# Picc.net
KiCad netlist of a schematic drawn in Altium Designer
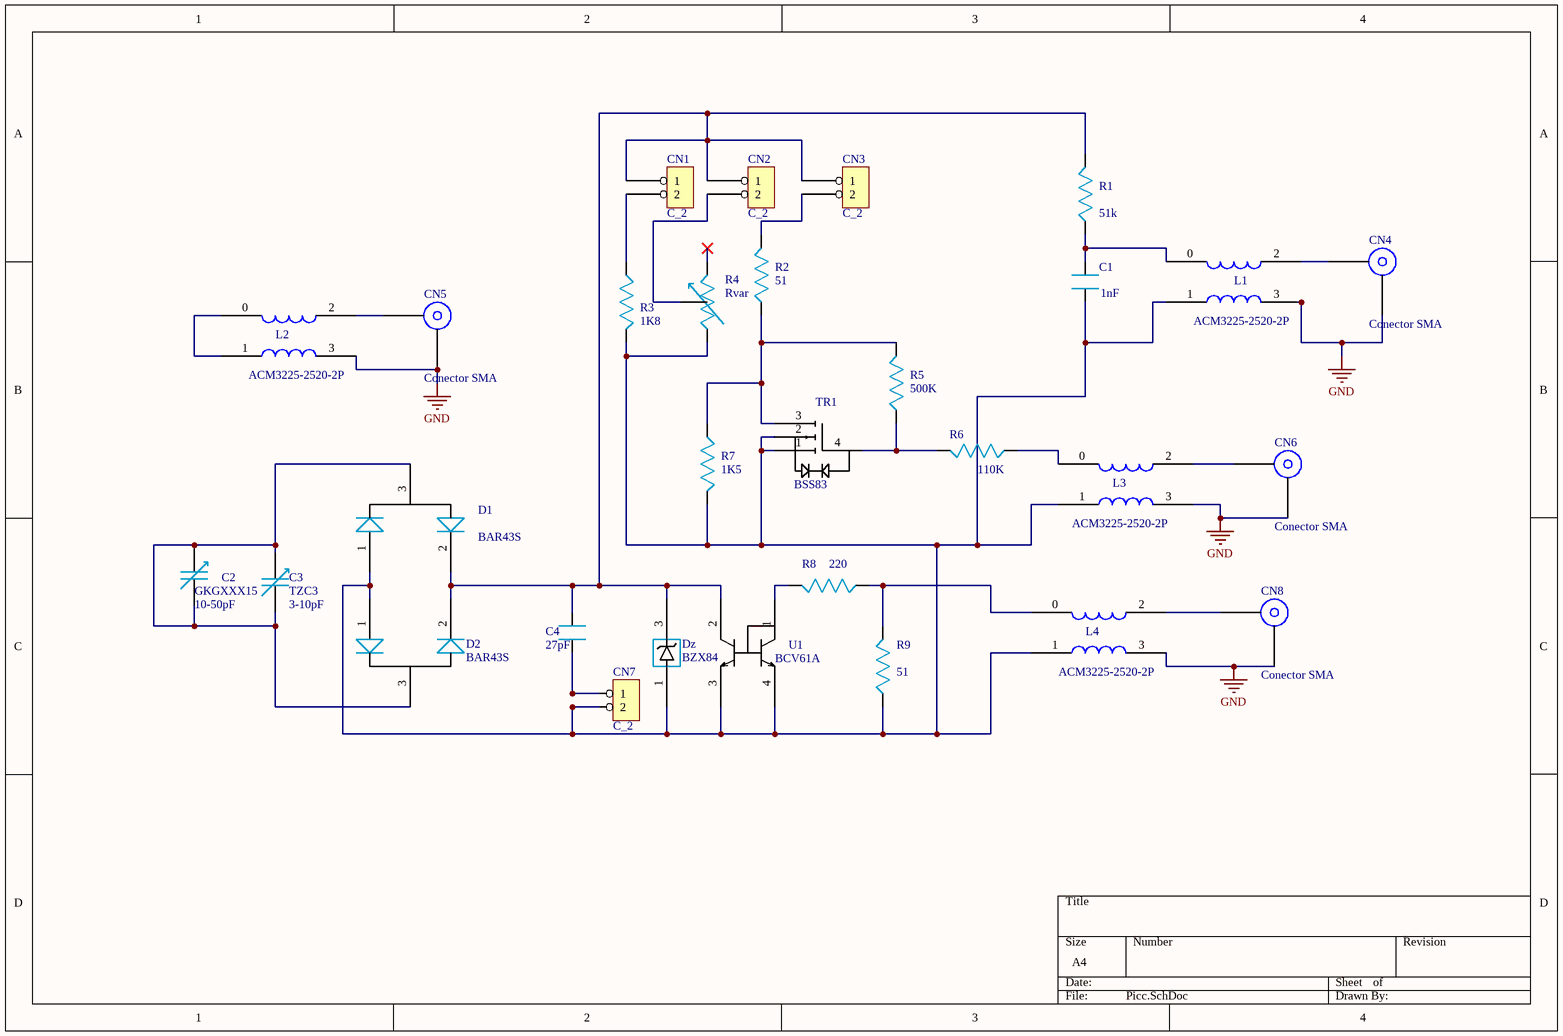
[diagram p0: Picc.SchDoc]

(export (version "E")
  (design (tool "Eeschema 10.0.6"))
  (components
    (comp (ref "C1")
      (value "1nF")
      (footprint "C_1210")
      (description "Ceramic Capacitor")
      (libsource (lib "BasicosyConectores") (part "Cap"))
    )
    (comp (ref "C2")
      (value "GKGXXX15")
      (footprint "GKGXXX15")
      (description "10")
      (fields (field (name "ALTIUM_UNNAMED_1") "10-50pF"))
      (libsource (lib "BasicosyConectores") (part "GKGXXX15"))
    )
    (comp (ref "C3")
      (value "TZC3")
      (footprint "TZC3")
      (fields (field (name "ALTIUM_UNNAMED_1") "3-10pF"))
      (libsource (lib "BasicosyConectores") (part "TZC3"))
    )
    (comp (ref "C4")
      (value "27pF")
      (footprint "C_1210")
      (description "Ceramic Capacitor")
      (libsource (lib "BasicosyConectores") (part "Cap"))
    )
    (comp (ref "CN1")
      (value "C_2")
      (footprint "2x1 Pin Array")
      (description "Conector 2 pines")
      (libsource (lib "BasicosyConectores") (part "C_2"))
    )
    (comp (ref "CN2")
      (value "C_2")
      (footprint "2x1 Pin Array")
      (description "Conector 2 pines")
      (libsource (lib "BasicosyConectores") (part "C_2"))
    )
    (comp (ref "CN3")
      (value "C_2")
      (footprint "2x1 Pin Array")
      (description "Conector 2 pines")
      (libsource (lib "BasicosyConectores") (part "C_2"))
    )
    (comp (ref "CN4")
      (value "Conector SMA")
      (footprint "Conector SMA")
      (description "Conector 2 pines")
      (libsource (lib "BasicosyConectores") (part "Conector SMA"))
    )
    (comp (ref "CN5")
      (value "Conector SMA")
      (footprint "Conector SMA")
      (description "Conector 2 pines")
      (libsource (lib "BasicosyConectores") (part "Conector SMA"))
    )
    (comp (ref "CN6")
      (value "Conector SMA")
      (footprint "Conector SMA")
      (description "Conector 2 pines")
      (libsource (lib "BasicosyConectores") (part "Conector SMA"))
    )
    (comp (ref "CN7")
      (value "C_2")
      (footprint "2x1 Pin Array")
      (description "Conector 2 pines")
      (libsource (lib "BasicosyConectores") (part "C_2"))
    )
    (comp (ref "CN8")
      (value "Conector SMA")
      (footprint "Conector SMA")
      (description "Conector 2 pines")
      (libsource (lib "BasicosyConectores") (part "Conector SMA"))
    )
    (comp (ref "D1")
      (value "BAR43S")
      (footprint "BAR43S")
      (libsource (lib "BasicosyConectores") (part "BAR43S"))
    )
    (comp (ref "D2")
      (value "BAR43S")
      (footprint "BAR43S")
      (libsource (lib "BasicosyConectores") (part "BAR43S"))
    )
    (comp (ref "Dz")
      (value "BZX84")
      (footprint "BZX84")
      (libsource (lib "BasicosyConectores") (part "BZX84"))
    )
    (comp (ref "L1")
      (value "ACM3225-2520-2P")
      (footprint "ACM3225.2520-2P")
      (libsource (lib "BasicosyConectores") (part "ACM3225-2520-2P"))
    )
    (comp (ref "L2")
      (value "ACM3225-2520-2P")
      (footprint "ACM3225.2520-2P")
      (libsource (lib "BasicosyConectores") (part "ACM3225-2520-2P"))
    )
    (comp (ref "L3")
      (value "ACM3225-2520-2P")
      (footprint "ACM3225.2520-2P")
      (libsource (lib "BasicosyConectores") (part "ACM3225-2520-2P"))
    )
    (comp (ref "L4")
      (value "ACM3225-2520-2P")
      (footprint "ACM3225.2520-2P")
      (libsource (lib "BasicosyConectores") (part "ACM3225-2520-2P"))
    )
    (comp (ref "R1")
      (value "51k")
      (footprint "R_1210")
      (description "Chip Resistor")
      (libsource (lib "BasicosyConectores") (part "R"))
    )
    (comp (ref "R2")
      (value "51")
      (footprint "R_1210")
      (description "Chip Resistor")
      (libsource (lib "BasicosyConectores") (part "R"))
    )
    (comp (ref "R3")
      (value "1K8")
      (footprint "R_1210")
      (description "Chip Resistor")
      (libsource (lib "BasicosyConectores") (part "R"))
    )
    (comp (ref "R4")
      (value "Rvar")
      (footprint "Bourns 3224W")
      (description "SMD Potentiometer")
      (libsource (lib "BasicosyConectores") (part "Rvar"))
    )
    (comp (ref "R5")
      (value "500K")
      (footprint "R_1210")
      (description "Chip Resistor")
      (libsource (lib "BasicosyConectores") (part "R"))
    )
    (comp (ref "R6")
      (value "110K")
      (footprint "R_1210")
      (description "Chip Resistor")
      (libsource (lib "BasicosyConectores") (part "R"))
    )
    (comp (ref "R7")
      (value "1K5")
      (footprint "R_1210")
      (description "Chip Resistor")
      (libsource (lib "BasicosyConectores") (part "R"))
    )
    (comp (ref "R8")
      (value "220")
      (footprint "R_1210")
      (description "Chip Resistor")
      (libsource (lib "BasicosyConectores") (part "R"))
    )
    (comp (ref "R9")
      (value "51")
      (footprint "R_1210")
      (description "Chip Resistor")
      (libsource (lib "BasicosyConectores") (part "R"))
    )
    (comp (ref "TR1")
      (value "BSS83")
      (footprint "BSS83")
      (libsource (lib "BasicosyConectores") (part "BSS83"))
    )
    (comp (ref "U1")
      (value "BCV61A")
      (footprint "BCV61A")
      (libsource (lib "BasicosyConectores") (part "BCV61A"))
    )
  )
  (nets
    (net (code "1") (name "GND") (class "Default")
      (node (ref "CN4") (pin "1") (pinfunction "1_1") (pintype "passive"))
      (node (ref "CN5") (pin "1") (pinfunction "1_1") (pintype "passive"))
      (node (ref "CN6") (pin "1") (pinfunction "1_1") (pintype "passive"))
      (node (ref "CN8") (pin "1") (pinfunction "1_1") (pintype "passive"))
      (node (ref "L1") (pin "3") (pinfunction "3_3") (pintype "passive"))
      (node (ref "L2") (pin "3") (pinfunction "3_3") (pintype "passive"))
      (node (ref "L3") (pin "3") (pinfunction "3_3") (pintype "passive"))
      (node (ref "L4") (pin "3") (pinfunction "3_3") (pintype "passive"))
    )
    (net (code "2") (name "Net-(C1-Pad2)") (class "Default")
      (node (ref "C1") (pin "2") (pinfunction "2_2") (pintype "passive"))
      (node (ref "L1") (pin "0") (pinfunction "0_0") (pintype "passive"))
      (node (ref "R1") (pin "1") (pinfunction "1_1") (pintype "passive"))
    )
    (net (code "3") (name "Net-(C2-Pad0)") (class "Default")
      (node (ref "C2") (pin "0") (pinfunction "0_0") (pintype "passive"))
      (node (ref "C2") (pin "1") (pinfunction "1_1") (pintype "passive"))
      (node (ref "C3") (pin "0") (pinfunction "0_0") (pintype "passive"))
      (node (ref "C3") (pin "1") (pinfunction "1_1") (pintype "passive"))
      (node (ref "D1") (pin "3") (pinfunction "3_3") (pintype "passive"))
      (node (ref "D2") (pin "3") (pinfunction "3_3") (pintype "passive"))
    )
    (net (code "4") (name "Net-(C4-Pad1)") (class "Default")
      (node (ref "C4") (pin "1") (pinfunction "1_1") (pintype "passive"))
      (node (ref "CN7") (pin "1") (pinfunction "1_1") (pintype "passive"))
    )
    (net (code "5") (name "Net-(C4-Pad2)") (class "Default")
      (node (ref "C4") (pin "2") (pinfunction "2_2") (pintype "passive"))
      (node (ref "CN1") (pin "1") (pinfunction "1_1") (pintype "passive"))
      (node (ref "CN2") (pin "1") (pinfunction "1_1") (pintype "passive"))
      (node (ref "CN3") (pin "1") (pinfunction "1_1") (pintype "passive"))
      (node (ref "D1") (pin "2") (pinfunction "2_2") (pintype "passive"))
      (node (ref "D2") (pin "2") (pinfunction "2_2") (pintype "passive"))
      (node (ref "Dz") (pin "3") (pinfunction "3_3") (pintype "passive"))
      (node (ref "R1") (pin "2") (pinfunction "2_2") (pintype "passive"))
      (node (ref "U1") (pin "2") (pinfunction "2_2") (pintype "passive"))
    )
    (net (code "6") (name "Net-(CN1-Pad2)") (class "Default")
      (node (ref "CN1") (pin "2") (pinfunction "2_2") (pintype "passive"))
      (node (ref "R3") (pin "1") (pinfunction "1_1") (pintype "passive"))
    )
    (net (code "7") (name "Net-(CN2-Pad2)") (class "Default")
      (node (ref "CN2") (pin "2") (pinfunction "2_2") (pintype "passive"))
      (node (ref "R4") (pin "3") (pinfunction "3_3") (pintype "passive"))
    )
    (net (code "8") (name "Net-(CN3-Pad2)") (class "Default")
      (node (ref "CN3") (pin "2") (pinfunction "2_2") (pintype "passive"))
      (node (ref "R2") (pin "2") (pinfunction "2_2") (pintype "passive"))
    )
    (net (code "9") (name "Net-(CN4-Pad0)") (class "Default")
      (node (ref "CN4") (pin "0") (pinfunction "0_0") (pintype "passive"))
      (node (ref "L1") (pin "2") (pinfunction "2_2") (pintype "passive"))
    )
    (net (code "10") (name "Net-(CN5-Pad0)") (class "Default")
      (node (ref "CN5") (pin "0") (pinfunction "0_0") (pintype "passive"))
      (node (ref "L2") (pin "2") (pinfunction "2_2") (pintype "passive"))
    )
    (net (code "11") (name "Net-(CN6-Pad0)") (class "Default")
      (node (ref "CN6") (pin "0") (pinfunction "0_0") (pintype "passive"))
      (node (ref "L3") (pin "2") (pinfunction "2_2") (pintype "passive"))
    )
    (net (code "12") (name "Net-(CN8-Pad0)") (class "Default")
      (node (ref "CN8") (pin "0") (pinfunction "0_0") (pintype "passive"))
      (node (ref "L4") (pin "2") (pinfunction "2_2") (pintype "passive"))
    )
    (net (code "13") (name "Net-(L2-Pad0)") (class "Default")
      (node (ref "L2") (pin "0") (pinfunction "0_0") (pintype "passive"))
      (node (ref "L2") (pin "1") (pinfunction "1_1") (pintype "passive"))
    )
    (net (code "14") (name "Net-(L3-Pad0)") (class "Default")
      (node (ref "L3") (pin "0") (pinfunction "0_0") (pintype "passive"))
      (node (ref "R6") (pin "1") (pinfunction "1_1") (pintype "passive"))
    )
    (net (code "15") (name "Net-(L4-Pad0)") (class "Default")
      (node (ref "L4") (pin "0") (pinfunction "0_0") (pintype "passive"))
      (node (ref "R8") (pin "1") (pinfunction "1_1") (pintype "passive"))
      (node (ref "R9") (pin "2") (pinfunction "2_2") (pintype "passive"))
    )
    (net (code "16") (name "Net-(R8-Pad2)") (class "Default")
      (node (ref "R8") (pin "2") (pinfunction "2_2") (pintype "passive"))
      (node (ref "U1") (pin "1") (pinfunction "1_1") (pintype "passive"))
    )
    (net (code "17") (name "Net-(TR1-b)") (class "Default")
      (node (ref "C1") (pin "1") (pinfunction "1_1") (pintype "passive"))
      (node (ref "CN7") (pin "2") (pinfunction "2_2") (pintype "passive"))
      (node (ref "D1") (pin "1") (pinfunction "1_1") (pintype "passive"))
      (node (ref "D2") (pin "1") (pinfunction "1_1") (pintype "passive"))
      (node (ref "Dz") (pin "1") (pinfunction "1_1") (pintype "passive"))
      (node (ref "L1") (pin "1") (pinfunction "1_1") (pintype "passive"))
      (node (ref "L3") (pin "1") (pinfunction "1_1") (pintype "passive"))
      (node (ref "L4") (pin "1") (pinfunction "1_1") (pintype "passive"))
      (node (ref "R3") (pin "2") (pinfunction "2_2") (pintype "passive"))
      (node (ref "R4") (pin "1") (pinfunction "1_1") (pintype "passive"))
      (node (ref "R7") (pin "2") (pinfunction "2_2") (pintype "passive"))
      (node (ref "R9") (pin "1") (pinfunction "1_1") (pintype "passive"))
      (node (ref "TR1") (pin "1") (pinfunction "s_1") (pintype "passive"))
      (node (ref "TR1") (pin "2") (pinfunction "b_2") (pintype "passive"))
      (node (ref "U1") (pin "3") (pinfunction "3_3") (pintype "passive"))
      (node (ref "U1") (pin "4") (pinfunction "4_4") (pintype "passive"))
    )
    (net (code "18") (name "Net-(TR1-d)") (class "Default")
      (node (ref "R2") (pin "1") (pinfunction "1_1") (pintype "passive"))
      (node (ref "R5") (pin "2") (pinfunction "2_2") (pintype "passive"))
      (node (ref "R7") (pin "1") (pinfunction "1_1") (pintype "passive"))
      (node (ref "TR1") (pin "3") (pinfunction "d_3") (pintype "passive"))
    )
    (net (code "19") (name "Net-(TR1-g)") (class "Default")
      (node (ref "R5") (pin "1") (pinfunction "1_1") (pintype "passive"))
      (node (ref "R6") (pin "2") (pinfunction "2_2") (pintype "passive"))
      (node (ref "TR1") (pin "4") (pinfunction "g_4") (pintype "passive"))
    )
    (net (code "20") (name "unconnected-(R4-Pad2)") (class "Default")
      (node (ref "R4") (pin "2") (pinfunction "2_2") (pintype "passive+no_connect"))
    )
  )
)
